# converter.net
KiCad netlist of a schematic drawn in EAGLE
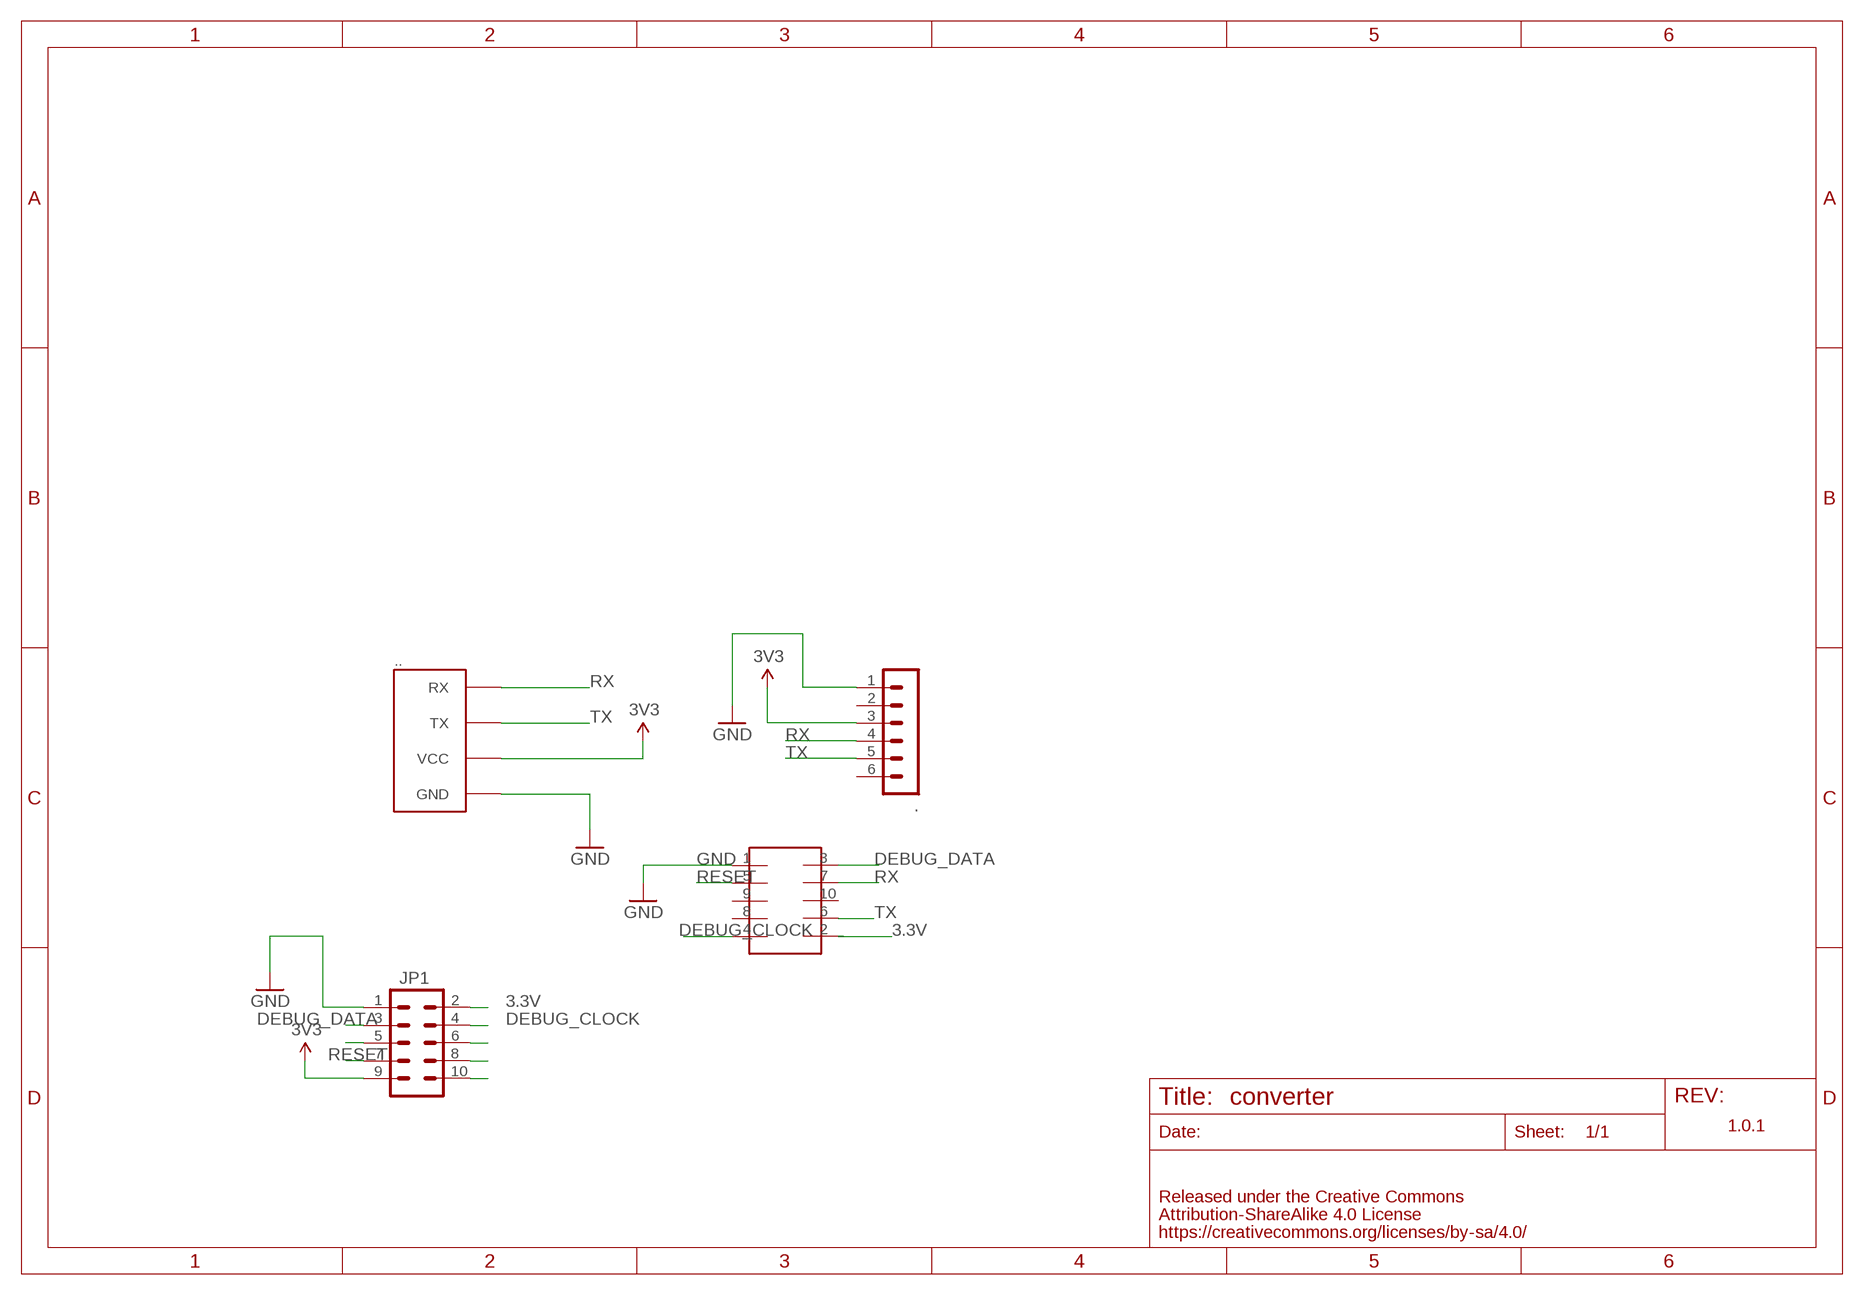
[diagram p0: schematic, sheet 1]

(export (version "E")
  (design (tool "Eeschema 10.0.6"))
  (components
    (comp (ref ".")
      (value "MA06-1")
      (footprint "eagle-import:MA06-1")
      (libsource (lib "eagle-import") (part "MA06-1"))
    )
    (comp (ref "..")
      (value "FABO_BRICK_SERIAL-S04B-PASK-2")
      (footprint "eagle-import:FABO_BRICK_SERIAL_S04B-PASK-2")
      (libsource (lib "eagle-import") (part "FABO_BRICK_SERIAL-S04B-PASK-2"))
    )
    (comp (ref "JP1")
      (value "M05X2SHD")
      (footprint "eagle-import:2X5-SHROUDED")
      (libsource (lib "eagle-import") (part "M05X2SHD"))
    )
    (comp (ref "U$4")
      (value "TC-2050-SOCKET")
      (footprint "eagle-import:TC-2050-SOCKET")
      (libsource (lib "eagle-import") (part "TC-2050-SOCKET"))
    )
  )
  (nets
    (net (code "1") (name "/3.3V") (class "Default")
      (node (ref "JP1") (pin "2") (pinfunction "2_2") (pintype "passive"))
      (node (ref "U$4") (pin "2") (pinfunction "2_2") (pintype "bidirectional"))
    )
    (net (code "2") (name "/DEBUG_CLOCK") (class "Default")
      (node (ref "JP1") (pin "4") (pinfunction "4_4") (pintype "passive"))
      (node (ref "U$4") (pin "4") (pinfunction "4_4") (pintype "bidirectional"))
    )
    (net (code "3") (name "/DEBUG_DATA") (class "Default")
      (node (ref "JP1") (pin "3") (pinfunction "3_3") (pintype "passive"))
      (node (ref "U$4") (pin "3") (pinfunction "3_3") (pintype "bidirectional"))
    )
    (net (code "4") (name "/RESET") (class "Default")
      (node (ref "JP1") (pin "7") (pinfunction "7_7") (pintype "passive"))
      (node (ref "U$4") (pin "5") (pinfunction "5_5") (pintype "bidirectional"))
    )
    (net (code "5") (name "/RX") (class "Default")
      (node (ref ".") (pin "4") (pinfunction "4_4") (pintype "passive"))
      (node (ref "..") (pin "RX") (pinfunction "RX_RX") (pintype "bidirectional"))
      (node (ref "U$4") (pin "7") (pinfunction "7_7") (pintype "bidirectional"))
    )
    (net (code "6") (name "/TX") (class "Default")
      (node (ref ".") (pin "5") (pinfunction "5_5") (pintype "passive"))
      (node (ref "..") (pin "TX") (pinfunction "TX_TX") (pintype "bidirectional"))
      (node (ref "U$4") (pin "6") (pinfunction "6_6") (pintype "bidirectional"))
    )
    (net (code "7") (name "3V3") (class "Default")
      (node (ref ".") (pin "3") (pinfunction "3_3") (pintype "passive"))
      (node (ref "..") (pin "VCC") (pinfunction "VCC_VCC") (pintype "bidirectional"))
      (node (ref "JP1") (pin "9") (pinfunction "9_9") (pintype "passive"))
    )
    (net (code "8") (name "GND") (class "Default")
      (node (ref ".") (pin "1") (pinfunction "1_1") (pintype "passive"))
      (node (ref "..") (pin "GND") (pinfunction "GND_GND") (pintype "bidirectional"))
      (node (ref "JP1") (pin "1") (pinfunction "1_1") (pintype "passive"))
      (node (ref "U$4") (pin "1") (pinfunction "1_1") (pintype "bidirectional"))
    )
    (net (code "9") (name "unconnected-(.-Pad2)") (class "Default")
      (node (ref ".") (pin "2") (pinfunction "2_2") (pintype "passive"))
    )
    (net (code "10") (name "unconnected-(.-Pad6)") (class "Default")
      (node (ref ".") (pin "6") (pinfunction "6_6") (pintype "passive"))
    )
    (net (code "11") (name "unconnected-(JP1-Pad5)") (class "Default")
      (node (ref "JP1") (pin "5") (pinfunction "5_5") (pintype "passive"))
    )
    (net (code "12") (name "unconnected-(JP1-Pad6)") (class "Default")
      (node (ref "JP1") (pin "6") (pinfunction "6_6") (pintype "passive"))
    )
    (net (code "13") (name "unconnected-(JP1-Pad8)") (class "Default")
      (node (ref "JP1") (pin "8") (pinfunction "8_8") (pintype "passive"))
    )
    (net (code "14") (name "unconnected-(JP1-Pad10)") (class "Default")
      (node (ref "JP1") (pin "10") (pinfunction "10_10") (pintype "passive"))
    )
    (net (code "15") (name "unconnected-(U$4-Pad8)") (class "Default")
      (node (ref "U$4") (pin "8") (pinfunction "8_8") (pintype "bidirectional"))
    )
    (net (code "16") (name "unconnected-(U$4-Pad9)") (class "Default")
      (node (ref "U$4") (pin "9") (pinfunction "9_9") (pintype "bidirectional"))
    )
    (net (code "17") (name "unconnected-(U$4-Pad10)") (class "Default")
      (node (ref "U$4") (pin "10") (pinfunction "10_10") (pintype "bidirectional"))
    )
  )
)
